# MCP4725_v14.net
KiCad netlist of a schematic drawn in EAGLE
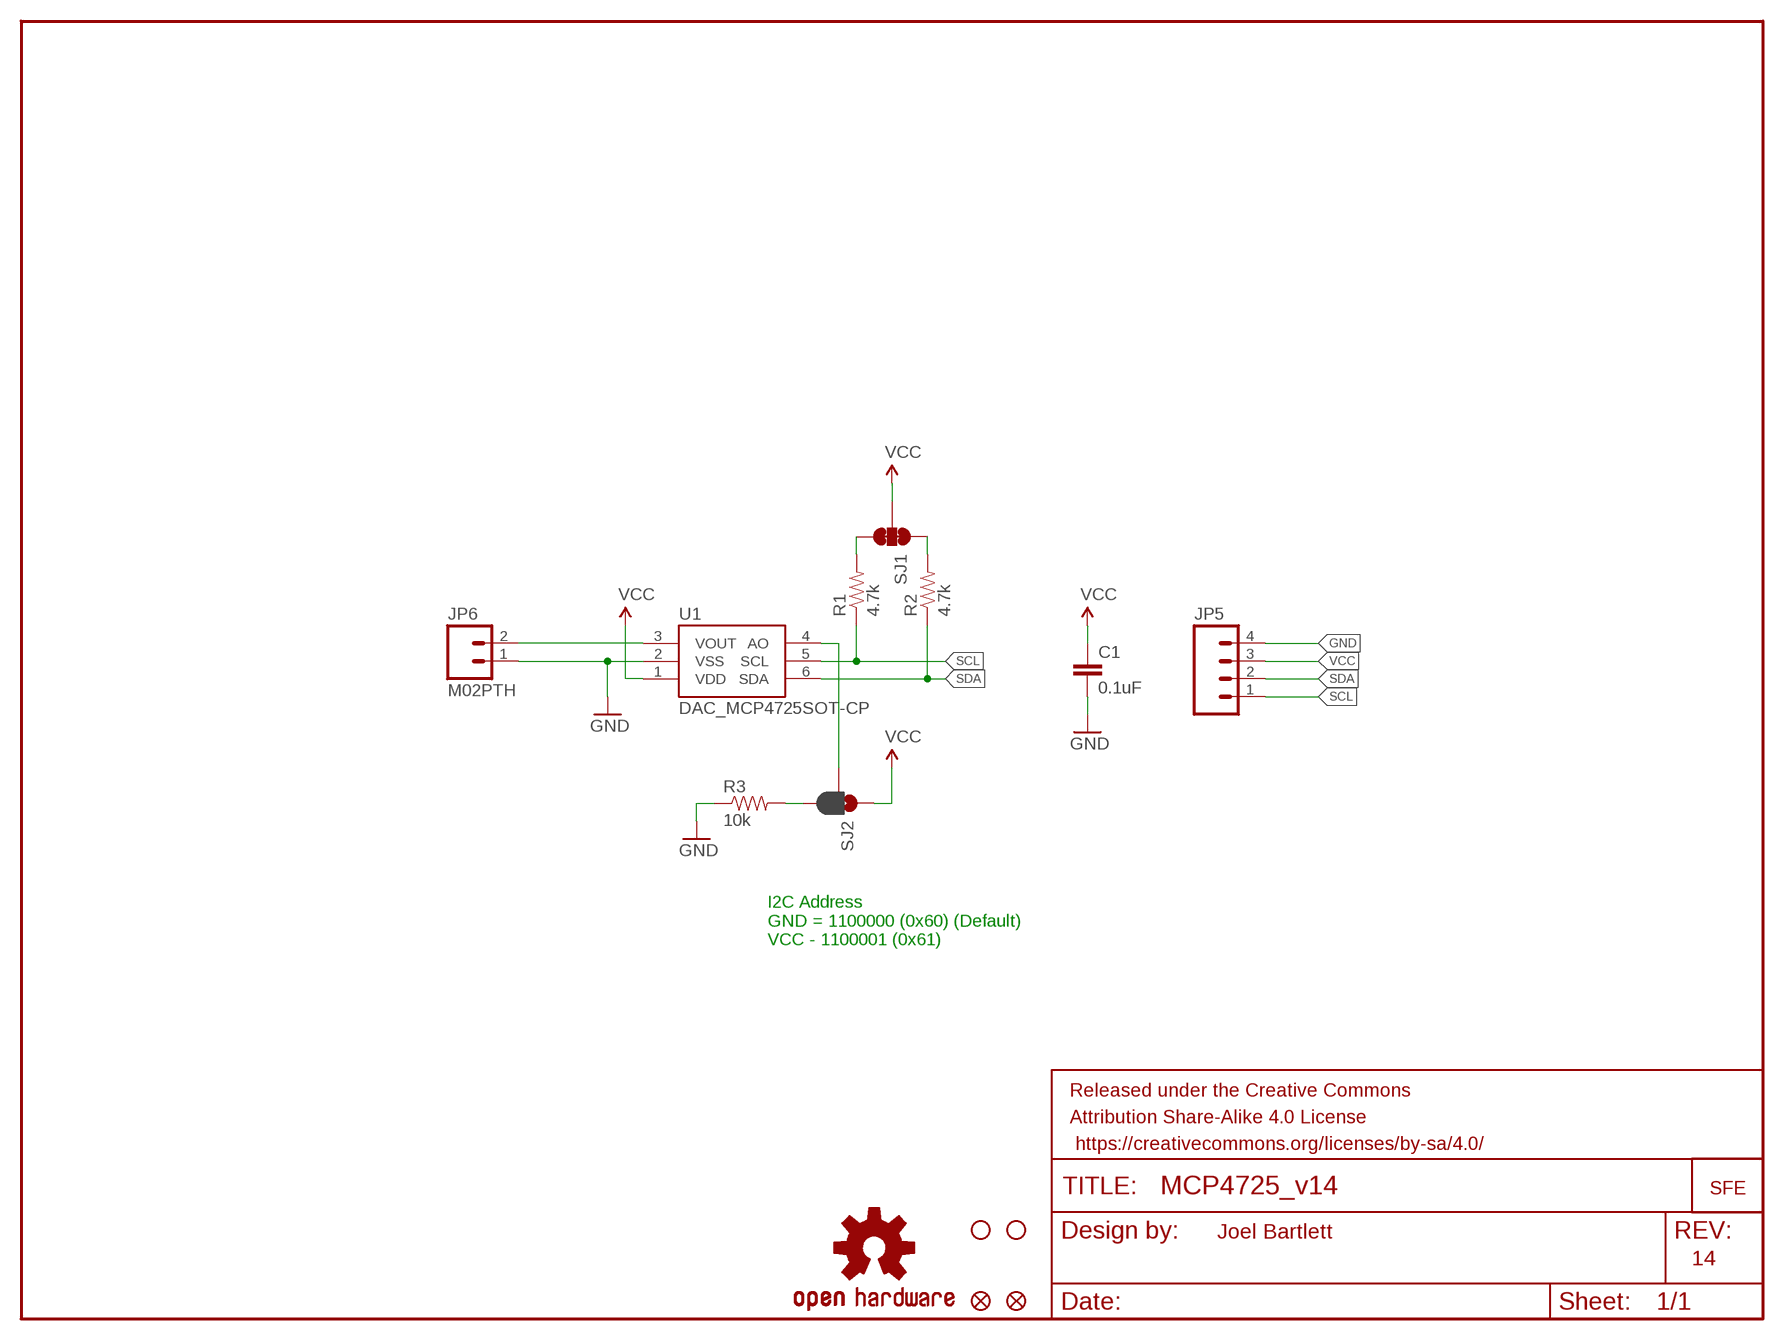
[diagram p0: schematic, sheet 1]

(export (version "E")
  (design (tool "Eeschema 10.0.6"))
  (components
    (comp (ref "C1")
      (value "0.1uF")
      (footprint "eagle-import:0603-CAP")
      (libsource (lib "eagle-import") (part "CAP0603-CAP"))
    )
    (comp (ref "FRAME2")
      (value "FRAME-LETTER")
      (footprint "eagle-import:CREATIVE_COMMONS")
      (libsource (lib "eagle-import") (part "FRAME-LETTER"))
    )
    (comp (ref "GND")
      (value "LOGO-SFESK")
      (footprint "eagle-import:SFE-LOGO-FLAME")
      (libsource (lib "eagle-import") (part "LOGO-SFESK"))
    )
    (comp (ref "JP2")
      (value "FIDUCIALUFIDUCIAL")
      (footprint "eagle-import:MICRO-FIDUCIAL")
      (libsource (lib "eagle-import") (part "FIDUCIALUFIDUCIAL"))
    )
    (comp (ref "JP3")
      (value "FIDUCIALUFIDUCIAL")
      (footprint "eagle-import:MICRO-FIDUCIAL")
      (libsource (lib "eagle-import") (part "FIDUCIALUFIDUCIAL"))
    )
    (comp (ref "JP5")
      (value "M04PTH")
      (footprint "eagle-import:1X04")
      (libsource (lib "eagle-import") (part "M04PTH"))
    )
    (comp (ref "JP6")
      (value "M02PTH")
      (footprint "eagle-import:1X02")
      (libsource (lib "eagle-import") (part "M02PTH"))
    )
    (comp (ref "LOGO1")
      (value "OSHW-LOGOS")
      (footprint "eagle-import:OSHW-LOGO-S")
      (libsource (lib "eagle-import") (part "OSHW-LOGOS"))
    )
    (comp (ref "R1")
      (value "4.7k")
      (footprint "eagle-import:0603-RES")
      (libsource (lib "eagle-import") (part "RESISTOR0603-RES"))
    )
    (comp (ref "R2")
      (value "4.7k")
      (footprint "eagle-import:0603-RES")
      (libsource (lib "eagle-import") (part "RESISTOR0603-RES"))
    )
    (comp (ref "R3")
      (value "10k")
      (footprint "eagle-import:0603-RES")
      (libsource (lib "eagle-import") (part "RESISTOR0603-RES"))
    )
    (comp (ref "SJ1")
      (value "JUMPER-PAD-3-NC_BY_TRACE")
      (footprint "eagle-import:PAD-JUMPER-3-3OF3_NC_BY_TRACE_YES_SILK_FULL_BOX")
      (libsource (lib "eagle-import") (part "JUMPER-PAD-3-NC_BY_TRACE"))
    )
    (comp (ref "SJ2")
      (value "JUMPER-PAD-3-2OF3_NC_BY_PASTE")
      (footprint "eagle-import:PAD-JUMPER-3-2OF3_NC_BY_PASTE_YES_SILK_FULL_BOX")
      (libsource (lib "eagle-import") (part "JUMPER-PAD-3-2OF3_NC_BY_PASTE"))
    )
    (comp (ref "STANDOFF1")
      (value "STAND-OFF")
      (footprint "eagle-import:STAND-OFF")
      (libsource (lib "eagle-import") (part "STAND-OFF"))
    )
    (comp (ref "STANDOFF2")
      (value "STAND-OFF")
      (footprint "eagle-import:STAND-OFF")
      (libsource (lib "eagle-import") (part "STAND-OFF"))
    )
    (comp (ref "U1")
      (value "DAC_MCP4725SOT-CP")
      (footprint "eagle-import:SOT23-6-MCP4725")
      (libsource (lib "eagle-import") (part "DAC_MCP4725SOT-CP"))
    )
  )
  (nets
    (net (code "1") (name "GND") (class "Default")
      (node (ref "C1") (pin "2") (pinfunction "2_2") (pintype "passive"))
      (node (ref "JP5") (pin "4") (pinfunction "4_4") (pintype "passive"))
      (node (ref "JP6") (pin "1") (pinfunction "1_1") (pintype "passive"))
      (node (ref "R3") (pin "1") (pinfunction "1_1") (pintype "passive"))
      (node (ref "U1") (pin "2") (pinfunction "VSS_2") (pintype "bidirectional"))
    )
    (net (code "2") (name "Net-(R1-Pad2)") (class "Default")
      (node (ref "R1") (pin "2") (pinfunction "2_2") (pintype "passive"))
      (node (ref "SJ1") (pin "3") (pinfunction "3_3") (pintype "passive"))
    )
    (net (code "3") (name "Net-(R2-Pad2)") (class "Default")
      (node (ref "R2") (pin "2") (pinfunction "2_2") (pintype "passive"))
      (node (ref "SJ1") (pin "1") (pinfunction "1_1") (pintype "passive"))
    )
    (net (code "4") (name "Net-(R3-Pad2)") (class "Default")
      (node (ref "R3") (pin "2") (pinfunction "2_2") (pintype "passive"))
      (node (ref "SJ2") (pin "3") (pinfunction "3_3") (pintype "passive"))
    )
    (net (code "5") (name "Net-(U1-AO)") (class "Default")
      (node (ref "SJ2") (pin "2") (pinfunction "2_2") (pintype "passive"))
      (node (ref "U1") (pin "4") (pinfunction "AO_4") (pintype "bidirectional"))
    )
    (net (code "6") (name "Net-(U1-VOUT)") (class "Default")
      (node (ref "JP6") (pin "2") (pinfunction "2_2") (pintype "passive"))
      (node (ref "U1") (pin "3") (pinfunction "VOUT_3") (pintype "bidirectional"))
    )
    (net (code "7") (name "SCL") (class "Default")
      (node (ref "JP5") (pin "1") (pinfunction "1_1") (pintype "passive"))
      (node (ref "R1") (pin "1") (pinfunction "1_1") (pintype "passive"))
      (node (ref "U1") (pin "5") (pinfunction "SCL_5") (pintype "bidirectional"))
    )
    (net (code "8") (name "SDA") (class "Default")
      (node (ref "JP5") (pin "2") (pinfunction "2_2") (pintype "passive"))
      (node (ref "R2") (pin "1") (pinfunction "1_1") (pintype "passive"))
      (node (ref "U1") (pin "6") (pinfunction "SDA_6") (pintype "bidirectional"))
    )
    (net (code "9") (name "VCC") (class "Default")
      (node (ref "C1") (pin "1") (pinfunction "1_1") (pintype "passive"))
      (node (ref "JP5") (pin "3") (pinfunction "3_3") (pintype "passive"))
      (node (ref "SJ1") (pin "2") (pinfunction "2_2") (pintype "passive"))
      (node (ref "SJ2") (pin "1") (pinfunction "1_1") (pintype "passive"))
      (node (ref "U1") (pin "1") (pinfunction "VDD_1") (pintype "bidirectional"))
    )
  )
)
